# EEPROM_ID.net
KiCad netlist of a schematic drawn in Altium Designer
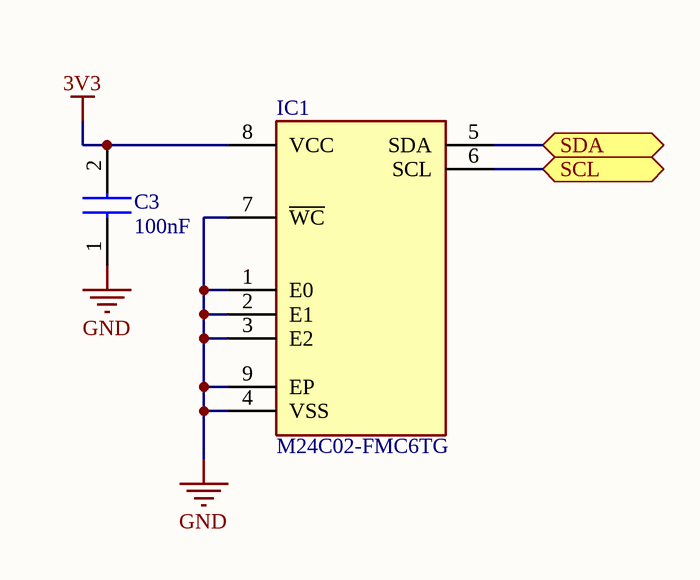
[diagram p0: EEPROM_ID.SchDoc]

(export (version "E")
  (design (tool "Eeschema 10.0.6"))
  (components
    (comp (ref "C3")
      (value "100nF")
      (footprint "SamacSys:CAPC1005X70N")
      (description "Capacitor")
      (fields
        (field (name "MANUFACTURER_PART_NUMBER") "GRM155R61A104KA01D")
        (field (name "MOUSER PART NUMBER") "81-GRM155R61A104KA01")
      )
      (libsource (lib "*") (part "GRM155R61A104KA01D"))
    )
    (comp (ref "IC1")
      (value "M24C02-FMC6TG")
      (footprint "SamacSys:M24C02FMC6TG")
      (description "Integrated Circuit")
      (fields (field (name "MOUSER PART NUMBER") "511-M24C02-FMC6TG"))
      (libsource (lib "SamacSys") (part "M24C02-FMC6TG"))
    )
  )
  (nets
    (net (code "1") (name "/SCL") (class "Default")
      (node (ref "IC1") (pin "6") (pinfunction "SCL_6") (pintype "passive"))
    )
    (net (code "2") (name "/SDA") (class "Default")
      (node (ref "IC1") (pin "5") (pinfunction "SDA_5") (pintype "passive"))
    )
    (net (code "3") (name "3V3") (class "Default")
      (node (ref "C3") (pin "2") (pinfunction "2_2") (pintype "passive"))
      (node (ref "IC1") (pin "8") (pinfunction "VCC_8") (pintype "passive"))
    )
    (net (code "4") (name "GND") (class "Default")
      (node (ref "C3") (pin "1") (pinfunction "1_1") (pintype "passive"))
      (node (ref "IC1") (pin "1") (pinfunction "E0_1") (pintype "passive"))
      (node (ref "IC1") (pin "2") (pinfunction "E1_2") (pintype "passive"))
      (node (ref "IC1") (pin "3") (pinfunction "E2_3") (pintype "passive"))
      (node (ref "IC1") (pin "4") (pinfunction "VSS_4") (pintype "passive"))
      (node (ref "IC1") (pin "7") (pinfunction "~{WC}_7") (pintype "passive"))
      (node (ref "IC1") (pin "9") (pinfunction "EP_9") (pintype "passive"))
    )
  )
)
